# fpga-bank8.net
KiCad netlist of a schematic drawn in Altium Designer
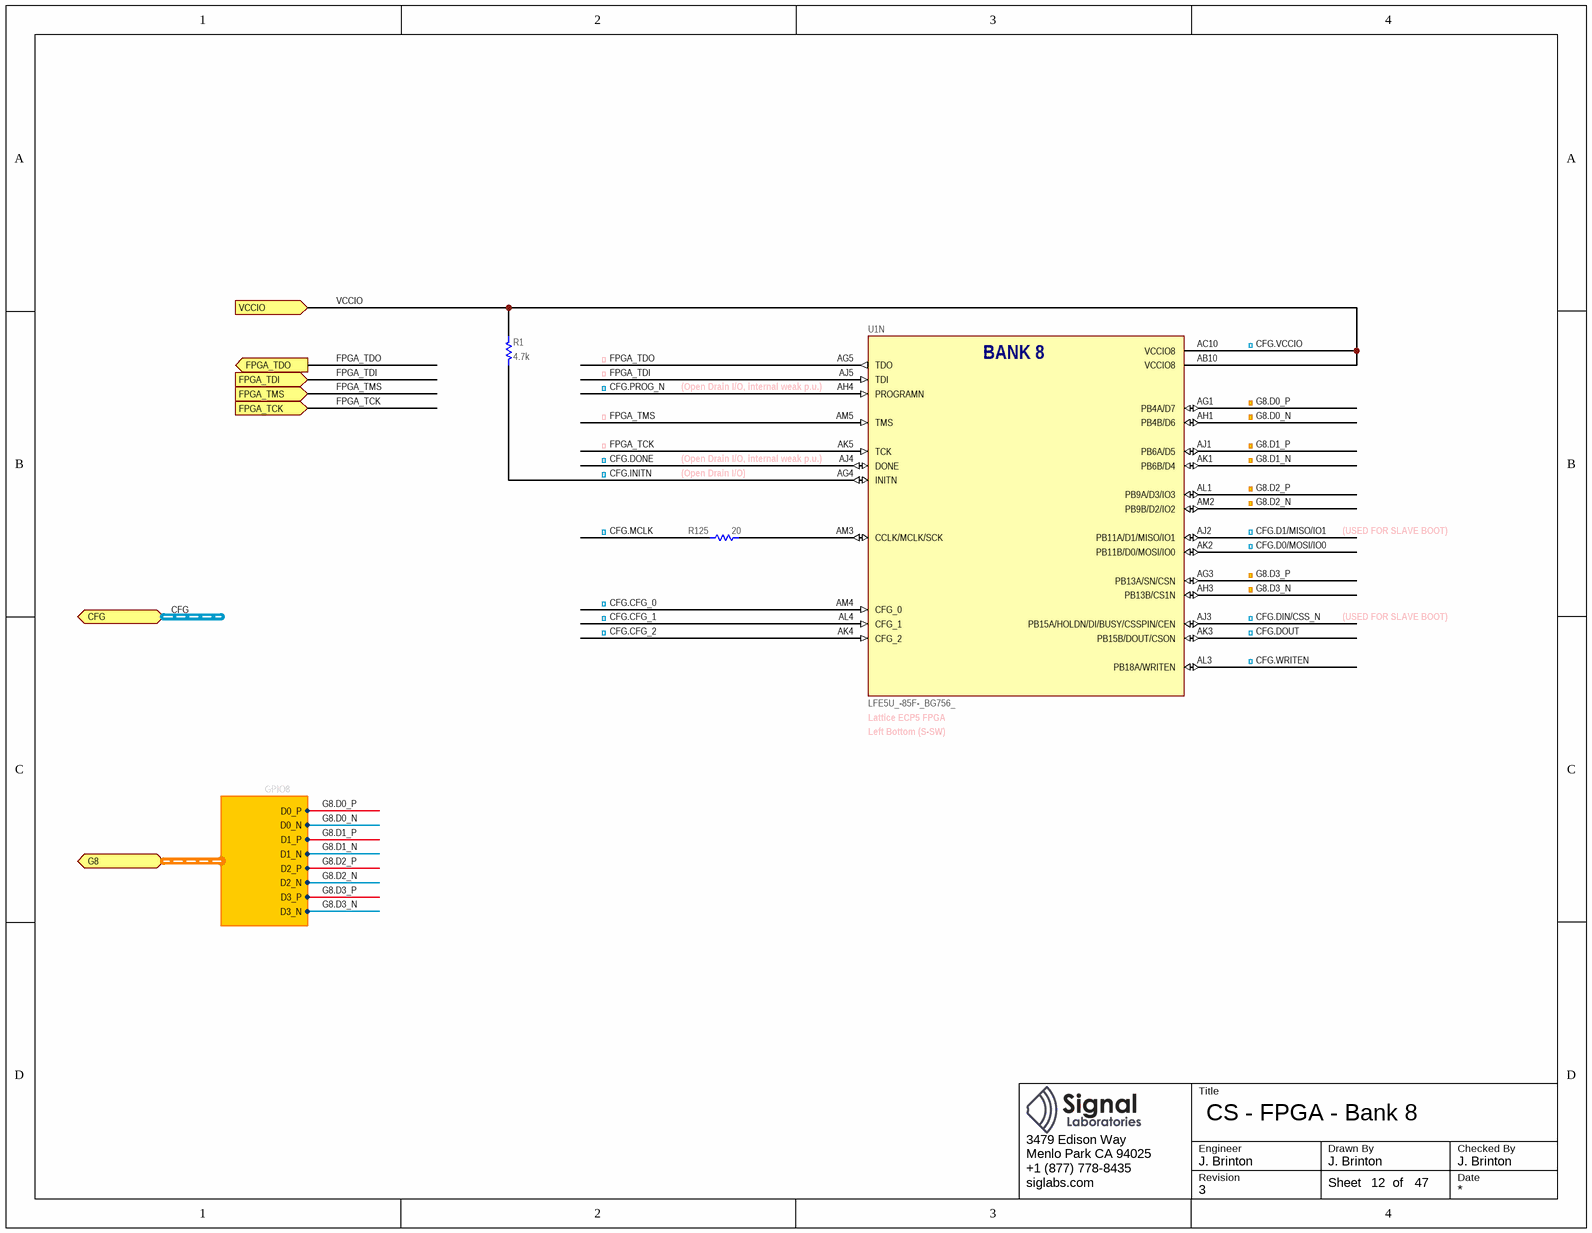
[diagram p0: fpga-bank8.SchDoc]

(export (version "E")
  (design (tool "Eeschema 10.0.6"))
  (components
    (comp (ref "R1")
      (value "4.7k")
      (footprint "RESC1005X40N")
      (description "Thick Film Resistor 4.7k ±1% 0.1W 75V 0402")
      (fields (field (name "TOLERANCE") "±1%") (field (name "MANUFACTURER") "Panasonic"))
      (libsource (lib "generic") (part "RES"))
    )
    (comp (ref "R125")
      (value "20")
      (footprint "RESC1005X40N")
      (description "Thick Film Resistor 20 ±1% 0.1W 75V 0402")
      (fields (field (name "TOLERANCE") "±1%") (field (name "MANUFACTURER") "Panasonic"))
      (libsource (lib "generic") (part "RES"))
    )
    (comp (ref "U1")
      (value "LFE5U_-85F-_BG756_")
      (footprint "lattice:caBGA756")
      (description "ECP5 FPGA, 85k LUT, 756-caBGA")
      (fields (field (name "MANUFACTURER") "Lattice Semiconductor"))
      (libsource (lib "lattice") (part "LFE5U_-85F-_BG756_"))
    )
  )
  (nets
    (net (code "3") (name "/CFG.CFG_0") (class "Default")
      (node (ref "U1") (pin "AM4") (pinfunction "CFG_0_AM4") (pintype "input"))
    )
    (net (code "4") (name "/CFG.CFG_1") (class "Default")
      (node (ref "U1") (pin "AL4") (pinfunction "CFG_1_AL4") (pintype "input"))
    )
    (net (code "5") (name "/CFG.CFG_2") (class "Default")
      (node (ref "U1") (pin "AK4") (pinfunction "CFG_2_AK4") (pintype "input"))
    )
    (net (code "6") (name "/CFG.D0{slash}MOSI{slash}IO0") (class "Default")
      (node (ref "U1") (pin "AK2") (pinfunction "PB11B/D0/MOSI/IO0_AK2") (pintype "bidirectional"))
    )
    (net (code "7") (name "/CFG.D1{slash}MISO{slash}IO1") (class "Default")
      (node (ref "U1") (pin "AJ2") (pinfunction "PB11A/D1/MISO/IO1_AJ2") (pintype "bidirectional"))
    )
    (net (code "8") (name "/CFG.DIN{slash}CSS_N") (class "Default")
      (node (ref "U1") (pin "AJ3") (pinfunction "PB15A/HOLDN/DI/BUSY/CSSPIN/CEN_AJ3") (pintype "bidirectional"))
    )
    (net (code "9") (name "/CFG.DONE") (class "Default")
      (node (ref "U1") (pin "AJ4") (pinfunction "DONE_AJ4") (pintype "bidirectional"))
    )
    (net (code "10") (name "/CFG.DOUT") (class "Default")
      (node (ref "U1") (pin "AK3") (pinfunction "PB15B/DOUT/CSON_AK3") (pintype "bidirectional"))
    )
    (net (code "11") (name "/CFG.INITN") (class "Default")
      (node (ref "R1") (pin "1") (pinfunction "1_1") (pintype "passive"))
      (node (ref "U1") (pin "AG4") (pinfunction "INITN_AG4") (pintype "bidirectional"))
    )
    (net (code "12") (name "/CFG.MCLK") (class "Default")
      (node (ref "R125") (pin "1") (pinfunction "1_1") (pintype "passive"))
    )
    (net (code "13") (name "/CFG.PROG_N") (class "Default")
      (node (ref "U1") (pin "AH4") (pinfunction "PROGRAMN_AH4") (pintype "input"))
    )
    (net (code "14") (name "/CFG.VCCIO") (class "Default")
      (node (ref "R1") (pin "2") (pinfunction "2_2") (pintype "passive"))
      (node (ref "U1") (pin "AB10") (pinfunction "VCCIO8_AB10") (pintype "power_in"))
      (node (ref "U1") (pin "AC10") (pinfunction "VCCIO8_AC10") (pintype "power_in"))
    )
    (net (code "15") (name "/CFG.WRITEN") (class "Default")
      (node (ref "U1") (pin "AL3") (pinfunction "PB18A/WRITEN_AL3") (pintype "bidirectional"))
    )
    (net (code "16") (name "/FPGA_TCK") (class "Default")
      (node (ref "U1") (pin "AK5") (pinfunction "TCK_AK5") (pintype "input"))
    )
    (net (code "17") (name "/FPGA_TDI") (class "Default")
      (node (ref "U1") (pin "AJ5") (pinfunction "TDI_AJ5") (pintype "input"))
    )
    (net (code "18") (name "/FPGA_TDO") (class "Default")
      (node (ref "U1") (pin "AG5") (pinfunction "TDO_AG5") (pintype "output"))
    )
    (net (code "19") (name "/FPGA_TMS") (class "Default")
      (node (ref "U1") (pin "AM5") (pinfunction "TMS_AM5") (pintype "input"))
    )
    (net (code "20") (name "/G8.D0_N") (class "Default")
      (node (ref "U1") (pin "AH1") (pinfunction "PB4B/D6_AH1") (pintype "bidirectional"))
    )
    (net (code "21") (name "/G8.D0_P") (class "Default")
      (node (ref "U1") (pin "AG1") (pinfunction "PB4A/D7_AG1") (pintype "bidirectional"))
    )
    (net (code "22") (name "/G8.D1_N") (class "Default")
      (node (ref "U1") (pin "AK1") (pinfunction "PB6B/D4_AK1") (pintype "bidirectional"))
    )
    (net (code "23") (name "/G8.D1_P") (class "Default")
      (node (ref "U1") (pin "AJ1") (pinfunction "PB6A/D5_AJ1") (pintype "bidirectional"))
    )
    (net (code "24") (name "/G8.D2_N") (class "Default")
      (node (ref "U1") (pin "AM2") (pinfunction "PB9B/D2/IO2_AM2") (pintype "bidirectional"))
    )
    (net (code "25") (name "/G8.D2_P") (class "Default")
      (node (ref "U1") (pin "AL1") (pinfunction "PB9A/D3/IO3_AL1") (pintype "bidirectional"))
    )
    (net (code "26") (name "/G8.D3_N") (class "Default")
      (node (ref "U1") (pin "AH3") (pinfunction "PB13B/CS1N_AH3") (pintype "bidirectional"))
    )
    (net (code "27") (name "/G8.D3_P") (class "Default")
      (node (ref "U1") (pin "AG3") (pinfunction "PB13A/SN/CSN_AG3") (pintype "bidirectional"))
    )
    (net (code "30") (name "Net-(U1N-CCLK{slash}MCLK{slash}SCK)") (class "Default")
      (node (ref "R125") (pin "2") (pinfunction "2_2") (pintype "passive"))
      (node (ref "U1") (pin "AM3") (pinfunction "CCLK/MCLK/SCK_AM3") (pintype "bidirectional"))
    )
  )
)
